# design.net
KiCad netlist of a schematic drawn in Altium Designer
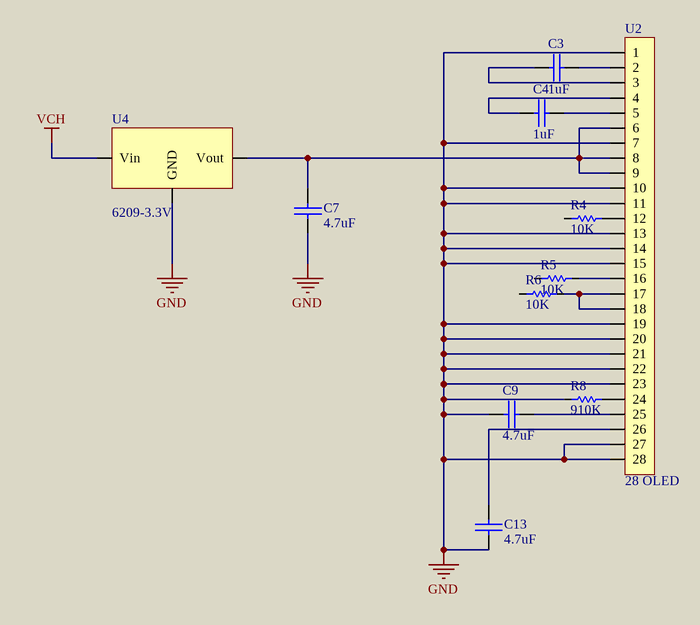
[diagram p0: 显示模块.SchDoc]

(export (version "E")
  (design (tool "Eeschema 10.0.6"))
  (components
    (comp (ref "C3")
      (value "1uF")
      (footprint "6-0805_L")
      (description "Capacitor")
      (libsource (lib "素材库") (part "CAP"))
    )
    (comp (ref "C4")
      (value "1uF")
      (footprint "6-0805_L")
      (description "Capacitor")
      (libsource (lib "素材库") (part "CAP"))
    )
    (comp (ref "C7")
      (value "4.7uF")
      (footprint "6-0805_L")
      (description "Capacitor")
      (libsource (lib "素材库") (part "CAP"))
    )
    (comp (ref "C9")
      (value "4.7uF")
      (footprint "6-0805_L")
      (description "Capacitor")
      (libsource (lib "素材库") (part "CAP"))
    )
    (comp (ref "C13")
      (value "4.7uF")
      (footprint "6-0805_L")
      (description "Capacitor")
      (libsource (lib "素材库") (part "CAP"))
    )
    (comp (ref "R4")
      (value "10K")
      (footprint "6-0805_L")
      (description "Resistor")
      (fields (field (name "PUBLISHER") "Altium Limited"))
      (libsource (lib "素材库") (part "Res1_1"))
    )
    (comp (ref "R5")
      (value "10K")
      (footprint "6-0805_L")
      (description "Resistor")
      (fields (field (name "PUBLISHER") "Altium Limited"))
      (libsource (lib "素材库") (part "Res1_1"))
    )
    (comp (ref "R6")
      (value "10K")
      (footprint "6-0805_L")
      (description "Resistor")
      (fields (field (name "PUBLISHER") "Altium Limited"))
      (libsource (lib "素材库") (part "Res1_1"))
    )
    (comp (ref "R8")
      (value "910K")
      (footprint "6-0805_L")
      (description "Resistor")
      (fields (field (name "PUBLISHER") "Altium Limited"))
      (libsource (lib "素材库") (part "Res1_1"))
    )
    (comp (ref "U2") (value "28 OLED") (footprint "28OLED") (libsource (lib "素材库") (part "28OLED")))
    (comp (ref "U4") (value "6209-3.3V") (footprint "SOT-23") (libsource (lib "素材库") (part "LDO")))
  )
  (nets
    (net (code "1") (name "GND") (class "Default")
      (node (ref "C13") (pin "2") (pinfunction "2_2") (pintype "passive"))
      (node (ref "C7") (pin "1") (pinfunction "1_1") (pintype "passive"))
      (node (ref "C9") (pin "2") (pinfunction "2_2") (pintype "passive"))
      (node (ref "R8") (pin "1") (pinfunction "1_1") (pintype "passive"))
      (node (ref "U2") (pin "1") (pinfunction "1_1") (pintype "passive"))
      (node (ref "U2") (pin "10") (pinfunction "10_10") (pintype "passive"))
      (node (ref "U2") (pin "11") (pinfunction "11_11") (pintype "passive"))
      (node (ref "U2") (pin "13") (pinfunction "13_13") (pintype "passive"))
      (node (ref "U2") (pin "14") (pinfunction "14_14") (pintype "passive"))
      (node (ref "U2") (pin "15") (pinfunction "15_15") (pintype "passive"))
      (node (ref "U2") (pin "19") (pinfunction "19_19") (pintype "passive"))
      (node (ref "U2") (pin "20") (pinfunction "20_20") (pintype "passive"))
      (node (ref "U2") (pin "21") (pinfunction "21_21") (pintype "passive"))
      (node (ref "U2") (pin "22") (pinfunction "22_22") (pintype "passive"))
      (node (ref "U2") (pin "23") (pinfunction "23_23") (pintype "passive"))
      (node (ref "U2") (pin "27") (pinfunction "27_27") (pintype "passive"))
      (node (ref "U2") (pin "28") (pinfunction "28_28") (pintype "passive"))
      (node (ref "U2") (pin "7") (pinfunction "7_7") (pintype "passive"))
      (node (ref "U4") (pin "1") (pinfunction "GND_1") (pintype "passive"))
    )
    (net (code "2") (name "Net-(C3-Pad1)") (class "Default")
      (node (ref "C3") (pin "1") (pinfunction "1_1") (pintype "passive"))
      (node (ref "U2") (pin "3") (pinfunction "3_3") (pintype "passive"))
    )
    (net (code "3") (name "Net-(C3-Pad2)") (class "Default")
      (node (ref "C3") (pin "2") (pinfunction "2_2") (pintype "passive"))
      (node (ref "U2") (pin "2") (pinfunction "2_2") (pintype "passive"))
    )
    (net (code "4") (name "Net-(C4-Pad1)") (class "Default")
      (node (ref "C4") (pin "1") (pinfunction "1_1") (pintype "passive"))
      (node (ref "U2") (pin "4") (pinfunction "4_4") (pintype "passive"))
    )
    (net (code "5") (name "Net-(C4-Pad2)") (class "Default")
      (node (ref "C4") (pin "2") (pinfunction "2_2") (pintype "passive"))
      (node (ref "U2") (pin "5") (pinfunction "5_5") (pintype "passive"))
    )
    (net (code "6") (name "Net-(C9-Pad1)") (class "Default")
      (node (ref "C9") (pin "1") (pinfunction "1_1") (pintype "passive"))
      (node (ref "U2") (pin "25") (pinfunction "25_25") (pintype "passive"))
    )
    (net (code "7") (name "Net-(C13-Pad1)") (class "Default")
      (node (ref "C13") (pin "1") (pinfunction "1_1") (pintype "passive"))
      (node (ref "U2") (pin "26") (pinfunction "26_26") (pintype "passive"))
    )
    (net (code "8") (name "Net-(R4-Pad2)") (class "Default")
      (node (ref "R4") (pin "2") (pinfunction "2_2") (pintype "passive"))
      (node (ref "U2") (pin "12") (pinfunction "12_12") (pintype "passive"))
    )
    (net (code "9") (name "Net-(R5-Pad2)") (class "Default")
      (node (ref "R5") (pin "2") (pinfunction "2_2") (pintype "passive"))
      (node (ref "U2") (pin "16") (pinfunction "16_16") (pintype "passive"))
    )
    (net (code "10") (name "Net-(R6-Pad2)") (class "Default")
      (node (ref "R6") (pin "2") (pinfunction "2_2") (pintype "passive"))
      (node (ref "U2") (pin "17") (pinfunction "17_17") (pintype "passive"))
      (node (ref "U2") (pin "18") (pinfunction "18_18") (pintype "passive"))
    )
    (net (code "11") (name "Net-(R8-Pad2)") (class "Default")
      (node (ref "R8") (pin "2") (pinfunction "2_2") (pintype "passive"))
      (node (ref "U2") (pin "24") (pinfunction "24_24") (pintype "passive"))
    )
    (net (code "12") (name "Net-(U4-Vout)") (class "Default")
      (node (ref "C7") (pin "2") (pinfunction "2_2") (pintype "passive"))
      (node (ref "U2") (pin "6") (pinfunction "6_6") (pintype "passive"))
      (node (ref "U2") (pin "8") (pinfunction "8_8") (pintype "passive"))
      (node (ref "U2") (pin "9") (pinfunction "9_9") (pintype "passive"))
      (node (ref "U4") (pin "2") (pinfunction "Vout_2") (pintype "passive"))
    )
    (net (code "13") (name "VCH") (class "Default")
      (node (ref "U4") (pin "3") (pinfunction "Vin_3") (pintype "passive"))
    )
    (net (code "14") (name "unconnected-(R4-Pad1)") (class "Default")
      (node (ref "R4") (pin "1") (pinfunction "1_1") (pintype "passive"))
    )
    (net (code "15") (name "unconnected-(R5-Pad1)") (class "Default")
      (node (ref "R5") (pin "1") (pinfunction "1_1") (pintype "passive"))
    )
    (net (code "16") (name "unconnected-(R6-Pad1)") (class "Default")
      (node (ref "R6") (pin "1") (pinfunction "1_1") (pintype "passive"))
    )
  )
)
